# DTMF.net
KiCad netlist of a schematic drawn in EAGLE
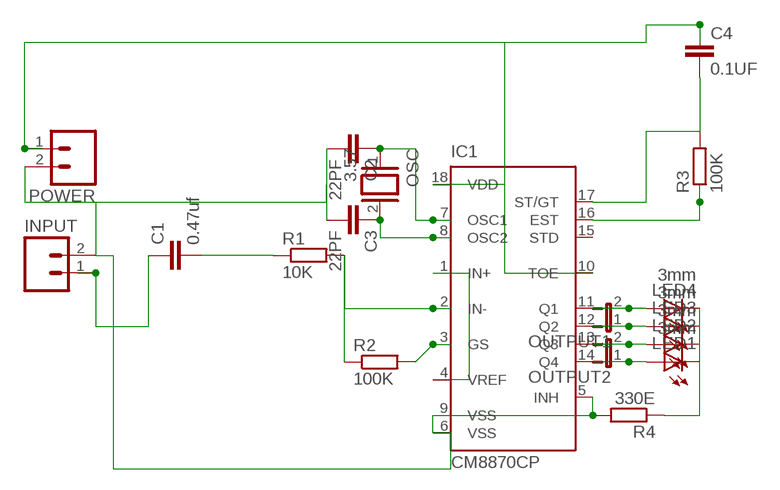
[diagram p0: schematic, sheet 1]

(export (version "E")
  (design (tool "Eeschema 10.0.6"))
  (components
    (comp (ref "C1")
      (value "0.47uf")
      (footprint "eagle-import:C2.5-2")
      (libsource (lib "eagle-import") (part "C2.5/2"))
    )
    (comp (ref "C2")
      (value "22PF")
      (footprint "eagle-import:C2.5-2")
      (libsource (lib "eagle-import") (part "C2.5/2"))
    )
    (comp (ref "C3")
      (value "22PF")
      (footprint "eagle-import:C2.5-2")
      (libsource (lib "eagle-import") (part "C2.5/2"))
    )
    (comp (ref "C4")
      (value "0.1UF")
      (footprint "eagle-import:C2.5-2")
      (libsource (lib "eagle-import") (part "C2.5/2"))
    )
    (comp (ref "IC1")
      (value "CM8870CP")
      (footprint "eagle-import:DIL18")
      (libsource (lib "eagle-import") (part "CM8870CP"))
    )
    (comp (ref "INPUT")
      (value "M02")
      (footprint "eagle-import:02P")
      (libsource (lib "eagle-import") (part "M02"))
    )
    (comp (ref "LED1")
      (value "3mm")
      (footprint "eagle-import:LED3MM")
      (libsource (lib "eagle-import") (part "LED3MM"))
    )
    (comp (ref "LED2")
      (value "3mm")
      (footprint "eagle-import:LED3MM")
      (libsource (lib "eagle-import") (part "LED3MM"))
    )
    (comp (ref "LED3")
      (value "3mm")
      (footprint "eagle-import:LED3MM")
      (libsource (lib "eagle-import") (part "LED3MM"))
    )
    (comp (ref "LED4")
      (value "3mm")
      (footprint "eagle-import:LED3MM")
      (libsource (lib "eagle-import") (part "LED3MM"))
    )
    (comp (ref "OSC")
      (value "3.57")
      (footprint "eagle-import:QS")
      (libsource (lib "eagle-import") (part "XTAL/S"))
    )
    (comp (ref "OUTPUT1")
      (value "JP1E")
      (footprint "eagle-import:JP1")
      (libsource (lib "eagle-import") (part "JP1E"))
    )
    (comp (ref "OUTPUT2")
      (value "JP1E")
      (footprint "eagle-import:JP1")
      (libsource (lib "eagle-import") (part "JP1E"))
    )
    (comp (ref "POWER")
      (value "M02")
      (footprint "eagle-import:02P")
      (libsource (lib "eagle-import") (part "M02"))
    )
    (comp (ref "R1")
      (value "10K")
      (footprint "eagle-import:0204_7")
      (libsource (lib "eagle-import") (part "R-EU_0204/7"))
    )
    (comp (ref "R2")
      (value "100K")
      (footprint "eagle-import:0204_7")
      (libsource (lib "eagle-import") (part "R-EU_0204/7"))
    )
    (comp (ref "R3")
      (value "100K")
      (footprint "eagle-import:0204_7")
      (libsource (lib "eagle-import") (part "R-EU_0204/7"))
    )
    (comp (ref "R4")
      (value "330E")
      (footprint "eagle-import:0204_7")
      (libsource (lib "eagle-import") (part "R-EU_0204/7"))
    )
  )
  (nets
    (net (code "1") (name "Net-(C1-Pad1)") (class "Default")
      (node (ref "C1") (pin "1") (pinfunction "1_1") (pintype "passive"))
      (node (ref "INPUT") (pin "1") (pinfunction "1_1") (pintype "passive"))
    )
    (net (code "2") (name "Net-(C1-Pad2)") (class "Default")
      (node (ref "C1") (pin "2") (pinfunction "2_2") (pintype "passive"))
      (node (ref "R1") (pin "1") (pinfunction "1_1") (pintype "passive"))
    )
    (net (code "3") (name "Net-(IC1-EST)") (class "Default")
      (node (ref "IC1") (pin "16") (pinfunction "EST_16") (pintype "input"))
      (node (ref "R3") (pin "1") (pinfunction "1_1") (pintype "passive"))
    )
    (net (code "4") (name "Net-(IC1-GS)") (class "Default")
      (node (ref "IC1") (pin "3") (pinfunction "GS_3") (pintype "input"))
      (node (ref "R2") (pin "2") (pinfunction "2_2") (pintype "passive"))
    )
    (net (code "5") (name "Net-(IC1-IN+)") (class "Default")
      (node (ref "IC1") (pin "1") (pinfunction "IN+_1") (pintype "input"))
      (node (ref "IC1") (pin "4") (pinfunction "VREF_4") (pintype "output"))
    )
    (net (code "6") (name "Net-(IC1-IN-)") (class "Default")
      (node (ref "IC1") (pin "2") (pinfunction "IN-_2") (pintype "input"))
      (node (ref "R1") (pin "2") (pinfunction "2_2") (pintype "passive"))
      (node (ref "R2") (pin "1") (pinfunction "1_1") (pintype "passive"))
    )
    (net (code "7") (name "Net-(IC1-INH)") (class "Default")
      (node (ref "C2") (pin "2") (pinfunction "2_2") (pintype "passive"))
      (node (ref "C3") (pin "2") (pinfunction "2_2") (pintype "passive"))
      (node (ref "IC1") (pin "5") (pinfunction "INH_5") (pintype "input"))
      (node (ref "IC1") (pin "6") (pinfunction "VSS_6") (pintype "power_in"))
      (node (ref "IC1") (pin "9") (pinfunction "VSS_9") (pintype "power_in"))
      (node (ref "INPUT") (pin "2") (pinfunction "2_2") (pintype "passive"))
      (node (ref "POWER") (pin "2") (pinfunction "2_2") (pintype "passive"))
      (node (ref "R4") (pin "2") (pinfunction "2_2") (pintype "passive"))
    )
    (net (code "8") (name "Net-(IC1-OSC1)") (class "Default")
      (node (ref "C2") (pin "1") (pinfunction "1_1") (pintype "passive"))
      (node (ref "IC1") (pin "7") (pinfunction "OSC1_7") (pintype "input"))
      (node (ref "OSC") (pin "1") (pinfunction "1_1") (pintype "passive"))
    )
    (net (code "9") (name "Net-(IC1-OSC2)") (class "Default")
      (node (ref "C3") (pin "1") (pinfunction "1_1") (pintype "passive"))
      (node (ref "IC1") (pin "8") (pinfunction "OSC2_8") (pintype "bidirectional"))
      (node (ref "OSC") (pin "2") (pinfunction "2_2") (pintype "passive"))
    )
    (net (code "10") (name "Net-(IC1-Q1)") (class "Default")
      (node (ref "IC1") (pin "11") (pinfunction "Q1_11") (pintype "output"))
      (node (ref "LED4") (pin "A") (pinfunction "A_A") (pintype "passive"))
      (node (ref "OUTPUT1") (pin "2") (pinfunction "2_2") (pintype "passive"))
    )
    (net (code "11") (name "Net-(IC1-Q2)") (class "Default")
      (node (ref "IC1") (pin "12") (pinfunction "Q2_12") (pintype "output"))
      (node (ref "LED3") (pin "A") (pinfunction "A_A") (pintype "passive"))
      (node (ref "OUTPUT1") (pin "1") (pinfunction "1_1") (pintype "passive"))
    )
    (net (code "12") (name "Net-(IC1-Q3)") (class "Default")
      (node (ref "IC1") (pin "13") (pinfunction "Q3_13") (pintype "output"))
      (node (ref "LED2") (pin "A") (pinfunction "A_A") (pintype "passive"))
      (node (ref "OUTPUT2") (pin "2") (pinfunction "2_2") (pintype "passive"))
    )
    (net (code "13") (name "Net-(IC1-Q4)") (class "Default")
      (node (ref "IC1") (pin "14") (pinfunction "Q4_14") (pintype "output"))
      (node (ref "LED1") (pin "A") (pinfunction "A_A") (pintype "passive"))
      (node (ref "OUTPUT2") (pin "1") (pinfunction "1_1") (pintype "passive"))
    )
    (net (code "14") (name "Net-(IC1-ST{slash}GT)") (class "Default")
      (node (ref "C4") (pin "2") (pinfunction "2_2") (pintype "passive"))
      (node (ref "IC1") (pin "17") (pinfunction "ST/GT_17") (pintype "bidirectional"))
      (node (ref "R3") (pin "2") (pinfunction "2_2") (pintype "passive"))
    )
    (net (code "15") (name "Net-(IC1-TOE)") (class "Default")
      (node (ref "C4") (pin "1") (pinfunction "1_1") (pintype "passive"))
      (node (ref "IC1") (pin "10") (pinfunction "TOE_10") (pintype "input"))
      (node (ref "IC1") (pin "18") (pinfunction "VDD_18") (pintype "power_in"))
      (node (ref "POWER") (pin "1") (pinfunction "1_1") (pintype "passive"))
    )
    (net (code "16") (name "Net-(LED1-C)") (class "Default")
      (node (ref "LED1") (pin "K") (pinfunction "C_K") (pintype "passive"))
      (node (ref "LED2") (pin "K") (pinfunction "C_K") (pintype "passive"))
      (node (ref "LED3") (pin "K") (pinfunction "C_K") (pintype "passive"))
      (node (ref "LED4") (pin "K") (pinfunction "C_K") (pintype "passive"))
      (node (ref "R4") (pin "1") (pinfunction "1_1") (pintype "passive"))
    )
    (net (code "17") (name "unconnected-(IC1-STD-Pad15)") (class "Default")
      (node (ref "IC1") (pin "15") (pinfunction "STD_15") (pintype "input"))
    )
  )
)
